# Sheet3.net
KiCad netlist of a schematic drawn in Altium Designer
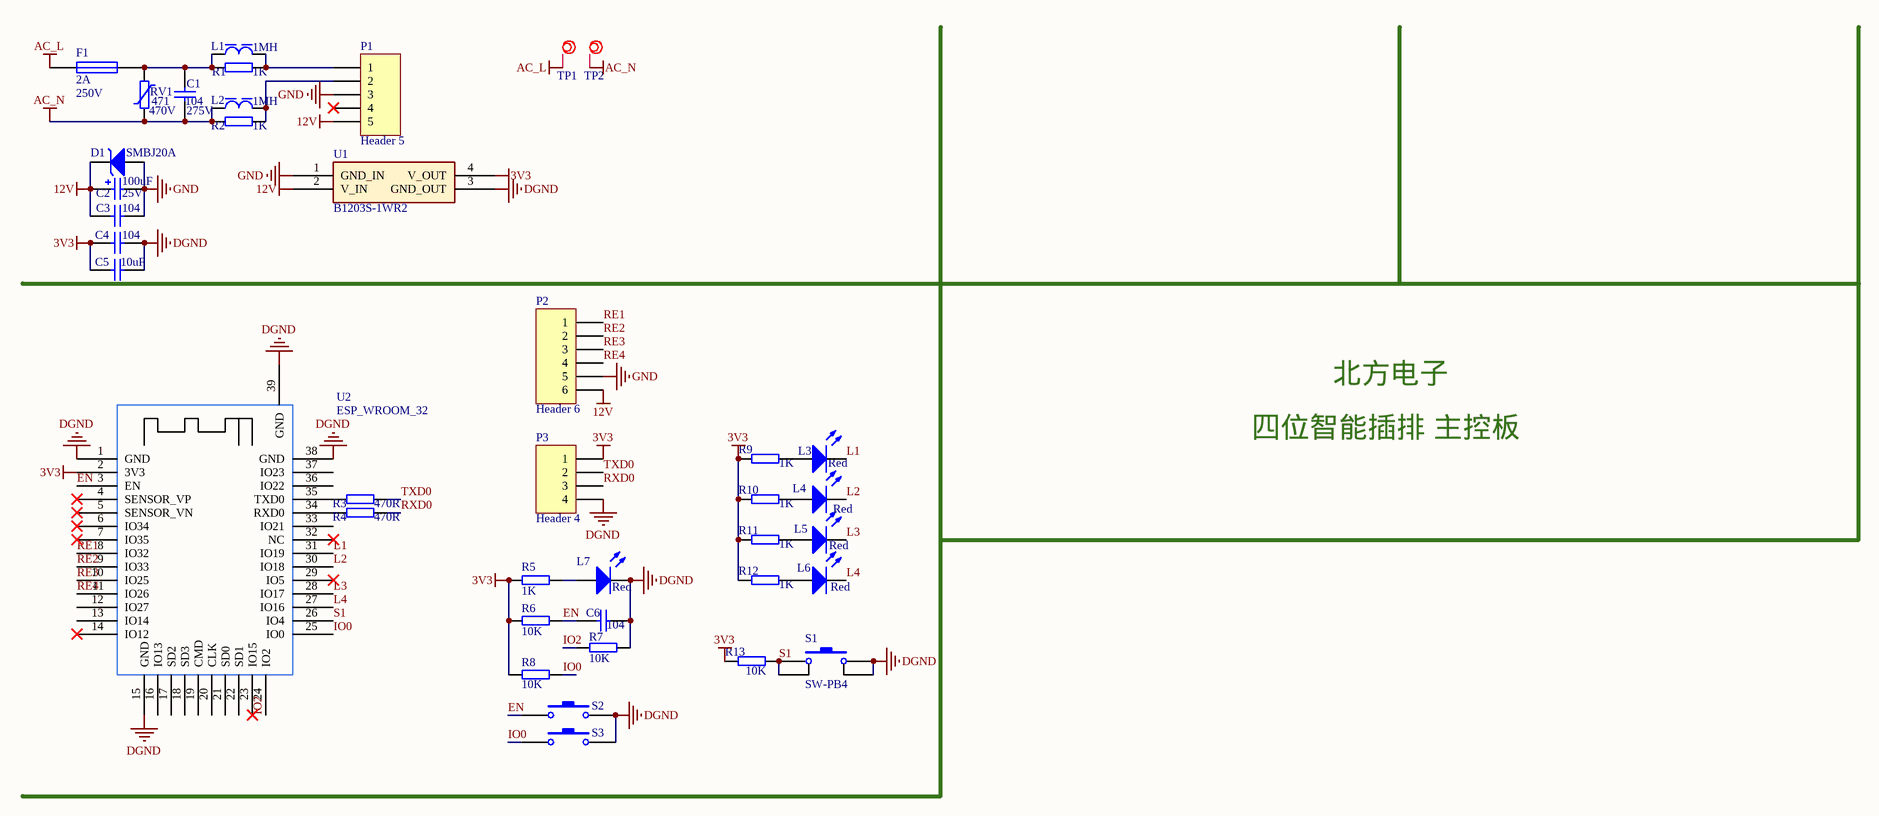
[diagram p0: Sheet3.SchDoc]

(export (version "E")
  (design (tool "Eeschema 10.0.6"))
  (components
    (comp (ref "C1")
      (value "104")
      (footprint "MPF131006")
      (description "Film Capacitor")
      (fields (field (name "VOLTAGE") "275V") (field (name "PUBLISHER") "Altium Limited"))
      (libsource (lib "!)Miscellaneous Integrated Library") (part "Cap Film 275VAC"))
    )
    (comp (ref "C2")
      (value "100uF")
      (footprint "CAPPR2.5-6.3X11.5")
      (description "Polarized Capacitor (Radial)")
      (fields (field (name "VOLTAGE") "25V") (field (name "PUBLISHER") "Altium Limited"))
      (libsource (lib "!)Miscellaneous Integrated Library") (part "Cap Pol 2.5-6.3"))
    )
    (comp (ref "C3")
      (value "104")
      (footprint "CAPC1005[0402]S")
      (description "Chip Capacitor, Silkscreen Border")
      (fields
        (field (name "VOLTAGE") "63V")
        (field (name "TOLERANCE") "Y5V")
        (field (name "PUBLISHER") "Altium Limited")
      )
      (libsource (lib "!)Miscellaneous Integrated Library") (part "Cap Chip 2"))
    )
    (comp (ref "C4")
      (value "104")
      (footprint "CAPC1005[0402]S")
      (description "Chip Capacitor, Silkscreen Border")
      (fields
        (field (name "VOLTAGE") "63V")
        (field (name "TOLERANCE") "Y5V")
        (field (name "PUBLISHER") "Altium Limited")
      )
      (libsource (lib "!)Miscellaneous Integrated Library") (part "Cap Chip 2"))
    )
    (comp (ref "C5")
      (value "10uF")
      (footprint "CAPC1005[0402]S")
      (description "Chip Capacitor, Silkscreen Border")
      (fields
        (field (name "VOLTAGE") "63V")
        (field (name "TOLERANCE") "Y5V")
        (field (name "PUBLISHER") "Altium Limited")
      )
      (libsource (lib "!)Miscellaneous Integrated Library") (part "Cap Chip 2"))
    )
    (comp (ref "C6")
      (value "104")
      (footprint "CAPC1005[0402]S")
      (description "Chip Capacitor, Silkscreen Border")
      (fields
        (field (name "VOLTAGE") "63V")
        (field (name "TOLERANCE") "Y5V")
        (field (name "PUBLISHER") "Altium Limited")
      )
      (libsource (lib "!)Miscellaneous Integrated Library") (part "Cap Chip 2"))
    )
    (comp (ref "D1")
      (value "SMBJ20A")
      (footprint "SMB[DO-214AA]")
      (description "TRANSIENT VOLTAGE  SUPPRESSOR DIODE")
      (fields (field (name "PARTNUMBER") "SMBJ20A") (field (name "PUBLISHER") "Altium Limited"))
      (libsource (lib "!)Miscellaneous Integrated Library") (part "Diode TVS Uni-Dir"))
    )
    (comp (ref "F1")
      (value "~")
      (footprint "FUSE-L")
      (description "Fuse")
      (fields
        (field (name "IMAX") "2A")
        (field (name "VOLTAGE") "250V")
        (field (name "PUBLISHER") "Altium Limited")
      )
      (libsource (lib "!)Miscellaneous Integrated Library") (part "Fuse"))
    )
    (comp (ref "L1")
      (value "1MH")
      (footprint "LGA0410")
      (description "Discrete Inductor, Ferrite-Core")
      (fields (field (name "PUBLISHER") "Altium Limited"))
      (libsource (lib "!)Miscellaneous Integrated Library") (part "Ind Axial"))
    )
    (comp (ref "L2")
      (value "1MH")
      (footprint "LGA0410")
      (description "Discrete Inductor, Ferrite-Core")
      (fields (field (name "PUBLISHER") "Altium Limited"))
      (libsource (lib "!)Miscellaneous Integrated Library") (part "Ind Axial"))
    )
    (comp (ref "L3")
      (value "Red")
      (footprint "LEDC1608(0603)")
      (description "Typical Chip LED")
      (fields (field (name "COLOR") "Red") (field (name "PUBLISHER") "Altium Limited"))
      (libsource (lib "!)Miscellaneous Integrated Library") (part "LED Chip"))
    )
    (comp (ref "L4")
      (value "Red")
      (footprint "LEDC1608(0603)")
      (description "Typical Chip LED")
      (fields (field (name "COLOR") "Red") (field (name "PUBLISHER") "Altium Limited"))
      (libsource (lib "!)Miscellaneous Integrated Library") (part "LED Chip"))
    )
    (comp (ref "L5")
      (value "Red")
      (footprint "LEDC1608(0603)")
      (description "Typical Chip LED")
      (fields (field (name "COLOR") "Red") (field (name "PUBLISHER") "Altium Limited"))
      (libsource (lib "!)Miscellaneous Integrated Library") (part "LED Chip"))
    )
    (comp (ref "L6")
      (value "Red")
      (footprint "LEDC1608(0603)")
      (description "Typical Chip LED")
      (fields (field (name "COLOR") "Red") (field (name "PUBLISHER") "Altium Limited"))
      (libsource (lib "!)Miscellaneous Integrated Library") (part "LED Chip"))
    )
    (comp (ref "L7")
      (value "Red")
      (footprint "LEDC1608(0603)")
      (description "Typical Chip LED")
      (fields (field (name "COLOR") "Red") (field (name "PUBLISHER") "Altium Limited"))
      (libsource (lib "!)Miscellaneous Integrated Library") (part "LED Chip"))
    )
    (comp (ref "P1")
      (value "Header 5")
      (footprint "AC-DC 12V 3W")
      (description "Header, 5-Pin")
      (fields (field (name "PUBLISHER") "Altium Limited"))
      (libsource (lib "!)Miscellaneous Integrated Library") (part "Header 5"))
    )
    (comp (ref "P2")
      (value "Header 6")
      (footprint "header 6 1.27mm")
      (description "Header, 6-Pin")
      (fields (field (name "PUBLISHER") "Altium Limited"))
      (libsource (lib "!)Miscellaneous Integrated Library") (part "Header 6"))
    )
    (comp (ref "P3")
      (value "Header 4")
      (footprint "HDR1X4")
      (description "Header, 4-Pin")
      (fields (field (name "PUBLISHER") "Altium Limited"))
      (libsource (lib "!)Miscellaneous Integrated Library") (part "Header 4"))
    )
    (comp (ref "R1")
      (value "1K")
      (footprint "RESC6332[2512]S")
      (description "Chip Resistor, Border Silkscreen On PCB Library")
      (fields (field (name "TOLERANCE") "5%") (field (name "PUBLISHER") "Altium Limited"))
      (libsource (lib "!)Miscellaneous Integrated Library") (part "Res Chip 2p 2"))
    )
    (comp (ref "R2")
      (value "1K")
      (footprint "RESC6332[2512]S")
      (description "Chip Resistor, Border Silkscreen On PCB Library")
      (fields (field (name "TOLERANCE") "5%") (field (name "PUBLISHER") "Altium Limited"))
      (libsource (lib "!)Miscellaneous Integrated Library") (part "Res Chip 2p 2"))
    )
    (comp (ref "R3")
      (value "470R")
      (footprint "RESC1005[0402]S")
      (description "Chip Resistor, Border Silkscreen On PCB Library")
      (fields (field (name "TOLERANCE") "5%") (field (name "PUBLISHER") "Altium Limited"))
      (libsource (lib "!)Miscellaneous Integrated Library") (part "Res Chip 2p 2"))
    )
    (comp (ref "R4")
      (value "470R")
      (footprint "RESC1005[0402]S")
      (description "Chip Resistor, Border Silkscreen On PCB Library")
      (fields (field (name "TOLERANCE") "5%") (field (name "PUBLISHER") "Altium Limited"))
      (libsource (lib "!)Miscellaneous Integrated Library") (part "Res Chip 2p 2"))
    )
    (comp (ref "R5")
      (value "1K")
      (footprint "RESC1005[0402]S")
      (description "Chip Resistor, Border Silkscreen On PCB Library")
      (fields (field (name "TOLERANCE") "5%") (field (name "PUBLISHER") "Altium Limited"))
      (libsource (lib "!)Miscellaneous Integrated Library") (part "Res Chip 2p 2"))
    )
    (comp (ref "R6")
      (value "10K")
      (footprint "RESC1005[0402]S")
      (description "Chip Resistor, Border Silkscreen On PCB Library")
      (fields (field (name "TOLERANCE") "5%") (field (name "PUBLISHER") "Altium Limited"))
      (libsource (lib "!)Miscellaneous Integrated Library") (part "Res Chip 2p 2"))
    )
    (comp (ref "R7")
      (value "10K")
      (footprint "RESC1005[0402]S")
      (description "Chip Resistor, Border Silkscreen On PCB Library")
      (fields (field (name "TOLERANCE") "5%") (field (name "PUBLISHER") "Altium Limited"))
      (libsource (lib "!)Miscellaneous Integrated Library") (part "Res Chip 2p 2"))
    )
    (comp (ref "R8")
      (value "10K")
      (footprint "RESC1005[0402]S")
      (description "Chip Resistor, Border Silkscreen On PCB Library")
      (fields (field (name "TOLERANCE") "5%") (field (name "PUBLISHER") "Altium Limited"))
      (libsource (lib "!)Miscellaneous Integrated Library") (part "Res Chip 2p 2"))
    )
    (comp (ref "R9")
      (value "1K")
      (footprint "RESC1005[0402]S")
      (description "Chip Resistor, Border Silkscreen On PCB Library")
      (fields (field (name "TOLERANCE") "5%") (field (name "PUBLISHER") "Altium Limited"))
      (libsource (lib "!)Miscellaneous Integrated Library") (part "Res Chip 2p 2"))
    )
    (comp (ref "R10")
      (value "1K")
      (footprint "RESC1005[0402]S")
      (description "Chip Resistor, Border Silkscreen On PCB Library")
      (fields (field (name "TOLERANCE") "5%") (field (name "PUBLISHER") "Altium Limited"))
      (libsource (lib "!)Miscellaneous Integrated Library") (part "Res Chip 2p 2"))
    )
    (comp (ref "R11")
      (value "1K")
      (footprint "RESC1005[0402]S")
      (description "Chip Resistor, Border Silkscreen On PCB Library")
      (fields (field (name "TOLERANCE") "5%") (field (name "PUBLISHER") "Altium Limited"))
      (libsource (lib "!)Miscellaneous Integrated Library") (part "Res Chip 2p 2"))
    )
    (comp (ref "R12")
      (value "1K")
      (footprint "RESC1005[0402]S")
      (description "Chip Resistor, Border Silkscreen On PCB Library")
      (fields (field (name "TOLERANCE") "5%") (field (name "PUBLISHER") "Altium Limited"))
      (libsource (lib "!)Miscellaneous Integrated Library") (part "Res Chip 2p 2"))
    )
    (comp (ref "R13")
      (value "10K")
      (footprint "RESC1005[0402]S")
      (description "Chip Resistor, Border Silkscreen On PCB Library")
      (fields (field (name "TOLERANCE") "5%") (field (name "PUBLISHER") "Altium Limited"))
      (libsource (lib "!)Miscellaneous Integrated Library") (part "Res Chip 2p 2"))
    )
    (comp (ref "RV1")
      (value "471")
      (footprint "RESKINK-E75W12")
      (description "Voltage Sense Resistor")
      (fields (field (name "VOLTAGE") "470V") (field (name "PUBLISHER") "Altium Limited"))
      (libsource (lib "!)Miscellaneous Integrated Library") (part "Res Varistor"))
    )
    (comp (ref "S1")
      (value "SW-PB4")
      (footprint "SW_PB4_A1")
      (description "微动开关")
      (fields (field (name "PUBLISHER") "Altium Limited"))
      (libsource (lib "Fszhang") (part "SW-PB4"))
    )
    (comp (ref "S2")
      (value "SW-PB")
      (footprint "button")
      (description "Switch")
      (fields (field (name "PUBLISHER") "Altium Limited"))
      (libsource (lib "!)Miscellaneous Integrated Library") (part "SW-PB"))
    )
    (comp (ref "S3")
      (value "SW-PB")
      (footprint "button")
      (description "Switch")
      (fields (field (name "PUBLISHER") "Altium Limited"))
      (libsource (lib "!)Miscellaneous Integrated Library") (part "SW-PB"))
    )
    (comp (ref "TP1")
      (value "Test Point")
      (footprint "TESTPOINT")
      (description "Test Point for Manufature")
      (libsource (lib "!)Miscellaneous Integrated Library") (part "Test Point"))
    )
    (comp (ref "TP2")
      (value "Test Point")
      (footprint "TESTPOINT")
      (description "Test Point for Manufature")
      (libsource (lib "!)Miscellaneous Integrated Library") (part "Test Point"))
    )
    (comp (ref "U1")
      (value "B1203S-1WR2")
      (footprint "B_S-1WR2")
      (libsource (lib "北方原理图库") (part "B_S-1WR2"))
    )
    (comp (ref "U2")
      (value "ESP_WROOM_32")
      (footprint "ESP32")
      (libsource (lib "北方原理图库") (part "ESP_WROOM_32"))
    )
  )
  (nets
    (net (code "1") (name "/EN") (class "Default")
      (node (ref "C6") (pin "2") (pinfunction "2_2") (pintype "passive"))
      (node (ref "R6") (pin "2") (pinfunction "2_2") (pintype "passive"))
      (node (ref "S2") (pin "1") (pinfunction "1_1") (pintype "passive"))
      (node (ref "U2") (pin "3") (pinfunction "EN_3") (pintype "passive"))
    )
    (net (code "2") (name "/IO0") (class "Default")
      (node (ref "R8") (pin "2") (pinfunction "2_2") (pintype "passive"))
      (node (ref "S3") (pin "1") (pinfunction "1_1") (pintype "passive"))
      (node (ref "U2") (pin "25") (pinfunction "IO0_25") (pintype "passive"))
    )
    (net (code "3") (name "/IO2") (class "Default")
      (node (ref "R7") (pin "1") (pinfunction "1_1") (pintype "passive"))
      (node (ref "U2") (pin "24") (pinfunction "IO2_24") (pintype "passive"))
    )
    (net (code "4") (name "/L1") (class "Default")
      (node (ref "L3") (pin "C") (pinfunction "C_C") (pintype "passive"))
      (node (ref "U2") (pin "31") (pinfunction "IO19_31") (pintype "passive"))
    )
    (net (code "5") (name "/L2") (class "Default")
      (node (ref "L4") (pin "C") (pinfunction "C_C") (pintype "passive"))
      (node (ref "U2") (pin "30") (pinfunction "IO18_30") (pintype "passive"))
    )
    (net (code "6") (name "/L3") (class "Default")
      (node (ref "L5") (pin "C") (pinfunction "C_C") (pintype "passive"))
      (node (ref "U2") (pin "28") (pinfunction "IO17_28") (pintype "passive"))
    )
    (net (code "7") (name "/L4") (class "Default")
      (node (ref "L6") (pin "C") (pinfunction "C_C") (pintype "passive"))
      (node (ref "U2") (pin "27") (pinfunction "IO16_27") (pintype "passive"))
    )
    (net (code "8") (name "/RE1") (class "Default")
      (node (ref "P2") (pin "1") (pinfunction "1_1") (pintype "passive"))
      (node (ref "U2") (pin "8") (pinfunction "IO32_8") (pintype "passive"))
    )
    (net (code "9") (name "/RE2") (class "Default")
      (node (ref "P2") (pin "2") (pinfunction "2_2") (pintype "passive"))
      (node (ref "U2") (pin "9") (pinfunction "IO33_9") (pintype "passive"))
    )
    (net (code "10") (name "/RE3") (class "Default")
      (node (ref "P2") (pin "3") (pinfunction "3_3") (pintype "passive"))
      (node (ref "U2") (pin "10") (pinfunction "IO25_10") (pintype "passive"))
    )
    (net (code "11") (name "/RE4") (class "Default")
      (node (ref "P2") (pin "4") (pinfunction "4_4") (pintype "passive"))
      (node (ref "U2") (pin "11") (pinfunction "IO26_11") (pintype "passive"))
    )
    (net (code "12") (name "/RXD0") (class "Default")
      (node (ref "P3") (pin "3") (pinfunction "3_3") (pintype "passive"))
      (node (ref "R4") (pin "2") (pinfunction "2_2") (pintype "passive"))
    )
    (net (code "13") (name "/S1") (class "Default")
      (node (ref "R13") (pin "2") (pinfunction "2_2") (pintype "passive"))
      (node (ref "S1") (pin "1") (pinfunction "1_1") (pintype "passive"))
      (node (ref "S1") (pin "4") (pinfunction "4_4") (pintype "passive"))
      (node (ref "U2") (pin "26") (pinfunction "IO4_26") (pintype "passive"))
    )
    (net (code "14") (name "/TXD0") (class "Default")
      (node (ref "P3") (pin "2") (pinfunction "2_2") (pintype "passive"))
      (node (ref "R3") (pin "2") (pinfunction "2_2") (pintype "passive"))
    )
    (net (code "15") (name "3V3") (class "Default")
      (node (ref "C4") (pin "1") (pinfunction "1_1") (pintype "passive"))
      (node (ref "C5") (pin "1") (pinfunction "1_1") (pintype "passive"))
      (node (ref "P3") (pin "1") (pinfunction "1_1") (pintype "passive"))
      (node (ref "R10") (pin "1") (pinfunction "1_1") (pintype "passive"))
      (node (ref "R11") (pin "1") (pinfunction "1_1") (pintype "passive"))
      (node (ref "R12") (pin "1") (pinfunction "1_1") (pintype "passive"))
      (node (ref "R13") (pin "1") (pinfunction "1_1") (pintype "passive"))
      (node (ref "R5") (pin "1") (pinfunction "1_1") (pintype "passive"))
      (node (ref "R6") (pin "1") (pinfunction "1_1") (pintype "passive"))
      (node (ref "R8") (pin "1") (pinfunction "1_1") (pintype "passive"))
      (node (ref "R9") (pin "1") (pinfunction "1_1") (pintype "passive"))
      (node (ref "U1") (pin "4") (pinfunction "V_OUT_4") (pintype "passive"))
      (node (ref "U2") (pin "2") (pinfunction "3V3_2") (pintype "passive"))
    )
    (net (code "16") (name "12V") (class "Default")
      (node (ref "C2") (pin "1") (pinfunction "1_1") (pintype "passive"))
      (node (ref "C3") (pin "1") (pinfunction "1_1") (pintype "passive"))
      (node (ref "D1") (pin "K") (pinfunction "K_K") (pintype "passive"))
      (node (ref "P1") (pin "5") (pinfunction "5_5") (pintype "passive"))
      (node (ref "P2") (pin "6") (pinfunction "6_6") (pintype "passive"))
      (node (ref "U1") (pin "2") (pinfunction "V_IN_2") (pintype "passive"))
    )
    (net (code "17") (name "AC_L") (class "Default")
      (node (ref "F1") (pin "1") (pinfunction "1_1") (pintype "passive"))
      (node (ref "TP1") (pin "1") (pinfunction "TP_1") (pintype "passive"))
    )
    (net (code "18") (name "AC_N") (class "Default")
      (node (ref "C1") (pin "1") (pinfunction "1_1") (pintype "passive"))
      (node (ref "L2") (pin "1") (pinfunction "1_1") (pintype "passive"))
      (node (ref "R2") (pin "1") (pinfunction "1_1") (pintype "passive"))
      (node (ref "RV1") (pin "1") (pinfunction "1_1") (pintype "passive"))
      (node (ref "TP2") (pin "1") (pinfunction "TP_1") (pintype "passive"))
    )
    (net (code "19") (name "DGND") (class "Default")
      (node (ref "C4") (pin "2") (pinfunction "2_2") (pintype "passive"))
      (node (ref "C5") (pin "2") (pinfunction "2_2") (pintype "passive"))
      (node (ref "C6") (pin "1") (pinfunction "1_1") (pintype "passive"))
      (node (ref "L7") (pin "C") (pinfunction "C_C") (pintype "passive"))
      (node (ref "P3") (pin "4") (pinfunction "4_4") (pintype "passive"))
      (node (ref "R7") (pin "2") (pinfunction "2_2") (pintype "passive"))
      (node (ref "S1") (pin "2") (pinfunction "2_2") (pintype "passive"))
      (node (ref "S1") (pin "3") (pinfunction "3_3") (pintype "passive"))
      (node (ref "S2") (pin "2") (pinfunction "2_2") (pintype "passive"))
      (node (ref "S3") (pin "2") (pinfunction "2_2") (pintype "passive"))
      (node (ref "U1") (pin "3") (pinfunction "GND_OUT_3") (pintype "passive"))
      (node (ref "U2") (pin "1") (pinfunction "GND_1") (pintype "passive"))
      (node (ref "U2") (pin "15") (pinfunction "GND_15") (pintype "passive"))
      (node (ref "U2") (pin "38") (pinfunction "GND_38") (pintype "passive"))
      (node (ref "U2") (pin "39") (pinfunction "GND_39") (pintype "passive"))
    )
    (net (code "20") (name "GND") (class "Default")
      (node (ref "C2") (pin "2") (pinfunction "2_2") (pintype "passive"))
      (node (ref "C3") (pin "2") (pinfunction "2_2") (pintype "passive"))
      (node (ref "D1") (pin "A") (pinfunction "A_A") (pintype "passive"))
      (node (ref "P1") (pin "3") (pinfunction "3_3") (pintype "passive"))
      (node (ref "P2") (pin "5") (pinfunction "5_5") (pintype "passive"))
      (node (ref "U1") (pin "1") (pinfunction "GND_IN_1") (pintype "passive"))
    )
    (net (code "21") (name "Net-(C1-Pad2)") (class "Default")
      (node (ref "C1") (pin "2") (pinfunction "2_2") (pintype "passive"))
      (node (ref "F1") (pin "2") (pinfunction "2_2") (pintype "passive"))
      (node (ref "L1") (pin "1") (pinfunction "1_1") (pintype "passive"))
      (node (ref "R1") (pin "1") (pinfunction "1_1") (pintype "passive"))
      (node (ref "RV1") (pin "2") (pinfunction "2_2") (pintype "passive"))
    )
    (net (code "22") (name "Net-(L1-Pad2)") (class "Default")
      (node (ref "L1") (pin "2") (pinfunction "2_2") (pintype "passive"))
      (node (ref "P1") (pin "1") (pinfunction "1_1") (pintype "passive"))
      (node (ref "R1") (pin "2") (pinfunction "2_2") (pintype "passive"))
    )
    (net (code "23") (name "Net-(L2-Pad2)") (class "Default")
      (node (ref "L2") (pin "2") (pinfunction "2_2") (pintype "passive"))
      (node (ref "P1") (pin "2") (pinfunction "2_2") (pintype "passive"))
      (node (ref "R2") (pin "2") (pinfunction "2_2") (pintype "passive"))
    )
    (net (code "24") (name "Net-(L3-PadA)") (class "Default")
      (node (ref "L3") (pin "A") (pinfunction "A_A") (pintype "passive"))
      (node (ref "R9") (pin "2") (pinfunction "2_2") (pintype "passive"))
    )
    (net (code "25") (name "Net-(L4-PadA)") (class "Default")
      (node (ref "L4") (pin "A") (pinfunction "A_A") (pintype "passive"))
      (node (ref "R10") (pin "2") (pinfunction "2_2") (pintype "passive"))
    )
    (net (code "26") (name "Net-(L5-PadA)") (class "Default")
      (node (ref "L5") (pin "A") (pinfunction "A_A") (pintype "passive"))
      (node (ref "R11") (pin "2") (pinfunction "2_2") (pintype "passive"))
    )
    (net (code "27") (name "Net-(L6-PadA)") (class "Default")
      (node (ref "L6") (pin "A") (pinfunction "A_A") (pintype "passive"))
      (node (ref "R12") (pin "2") (pinfunction "2_2") (pintype "passive"))
    )
    (net (code "28") (name "Net-(L7-PadA)") (class "Default")
      (node (ref "L7") (pin "A") (pinfunction "A_A") (pintype "passive"))
      (node (ref "R5") (pin "2") (pinfunction "2_2") (pintype "passive"))
    )
    (net (code "29") (name "Net-(U2-RXD0)") (class "Default")
      (node (ref "R4") (pin "1") (pinfunction "1_1") (pintype "passive"))
      (node (ref "U2") (pin "34") (pinfunction "RXD0_34") (pintype "passive"))
    )
    (net (code "30") (name "Net-(U2-TXD0)") (class "Default")
      (node (ref "R3") (pin "1") (pinfunction "1_1") (pintype "passive"))
      (node (ref "U2") (pin "35") (pinfunction "TXD0_35") (pintype "passive"))
    )
    (net (code "31") (name "unconnected-(P1-Pad4)") (class "Default")
      (node (ref "P1") (pin "4") (pinfunction "4_4") (pintype "passive+no_connect"))
    )
    (net (code "32") (name "unconnected-(U2-CLK-Pad20)") (class "Default")
      (node (ref "U2") (pin "20") (pinfunction "CLK_20") (pintype "passive"))
    )
    (net (code "33") (name "unconnected-(U2-CMD-Pad19)") (class "Default")
      (node (ref "U2") (pin "19") (pinfunction "CMD_19") (pintype "passive"))
    )
    (net (code "34") (name "unconnected-(U2-IO5-Pad29)") (class "Default")
      (node (ref "U2") (pin "29") (pinfunction "IO5_29") (pintype "passive+no_connect"))
    )
    (net (code "35") (name "unconnected-(U2-IO12-Pad14)") (class "Default")
      (node (ref "U2") (pin "14") (pinfunction "IO12_14") (pintype "passive+no_connect"))
    )
    (net (code "36") (name "unconnected-(U2-IO13-Pad16)") (class "Default")
      (node (ref "U2") (pin "16") (pinfunction "IO13_16") (pintype "passive"))
    )
    (net (code "37") (name "unconnected-(U2-IO14-Pad13)") (class "Default")
      (node (ref "U2") (pin "13") (pinfunction "IO14_13") (pintype "passive"))
    )
    (net (code "38") (name "unconnected-(U2-IO15-Pad23)") (class "Default")
      (node (ref "U2") (pin "23") (pinfunction "IO15_23") (pintype "passive+no_connect"))
    )
    (net (code "39") (name "unconnected-(U2-IO21-Pad33)") (class "Default")
      (node (ref "U2") (pin "33") (pinfunction "IO21_33") (pintype "passive"))
    )
    (net (code "40") (name "unconnected-(U2-IO22-Pad36)") (class "Default")
      (node (ref "U2") (pin "36") (pinfunction "IO22_36") (pintype "passive"))
    )
    (net (code "41") (name "unconnected-(U2-IO23-Pad37)") (class "Default")
      (node (ref "U2") (pin "37") (pinfunction "IO23_37") (pintype "passive"))
    )
    (net (code "42") (name "unconnected-(U2-IO27-Pad12)") (class "Default")
      (node (ref "U2") (pin "12") (pinfunction "IO27_12") (pintype "passive"))
    )
    (net (code "43") (name "unconnected-(U2-IO34-Pad6)") (class "Default")
      (node (ref "U2") (pin "6") (pinfunction "IO34_6") (pintype "passive+no_connect"))
    )
    (net (code "44") (name "unconnected-(U2-IO35-Pad7)") (class "Default")
      (node (ref "U2") (pin "7") (pinfunction "IO35_7") (pintype "passive+no_connect"))
    )
    (net (code "45") (name "unconnected-(U2-NC-Pad32)") (class "Default")
      (node (ref "U2") (pin "32") (pinfunction "NC_32") (pintype "passive+no_connect"))
    )
    (net (code "46") (name "unconnected-(U2-SD0-Pad21)") (class "Default")
      (node (ref "U2") (pin "21") (pinfunction "SD0_21") (pintype "passive"))
    )
    (net (code "47") (name "unconnected-(U2-SD1-Pad22)") (class "Default")
      (node (ref "U2") (pin "22") (pinfunction "SD1_22") (pintype "passive"))
    )
    (net (code "48") (name "unconnected-(U2-SD2-Pad17)") (class "Default")
      (node (ref "U2") (pin "17") (pinfunction "SD2_17") (pintype "passive"))
    )
    (net (code "49") (name "unconnected-(U2-SD3-Pad18)") (class "Default")
      (node (ref "U2") (pin "18") (pinfunction "SD3_18") (pintype "passive"))
    )
    (net (code "50") (name "unconnected-(U2-SENSOR_VN-Pad5)") (class "Default")
      (node (ref "U2") (pin "5") (pinfunction "SENSOR_VN_5") (pintype "passive+no_connect"))
    )
    (net (code "51") (name "unconnected-(U2-SENSOR_VP-Pad4)") (class "Default")
      (node (ref "U2") (pin "4") (pinfunction "SENSOR_VP_4") (pintype "passive+no_connect"))
    )
  )
)
